# Lighting_Board.net
KiCad netlist of a schematic drawn in EAGLE
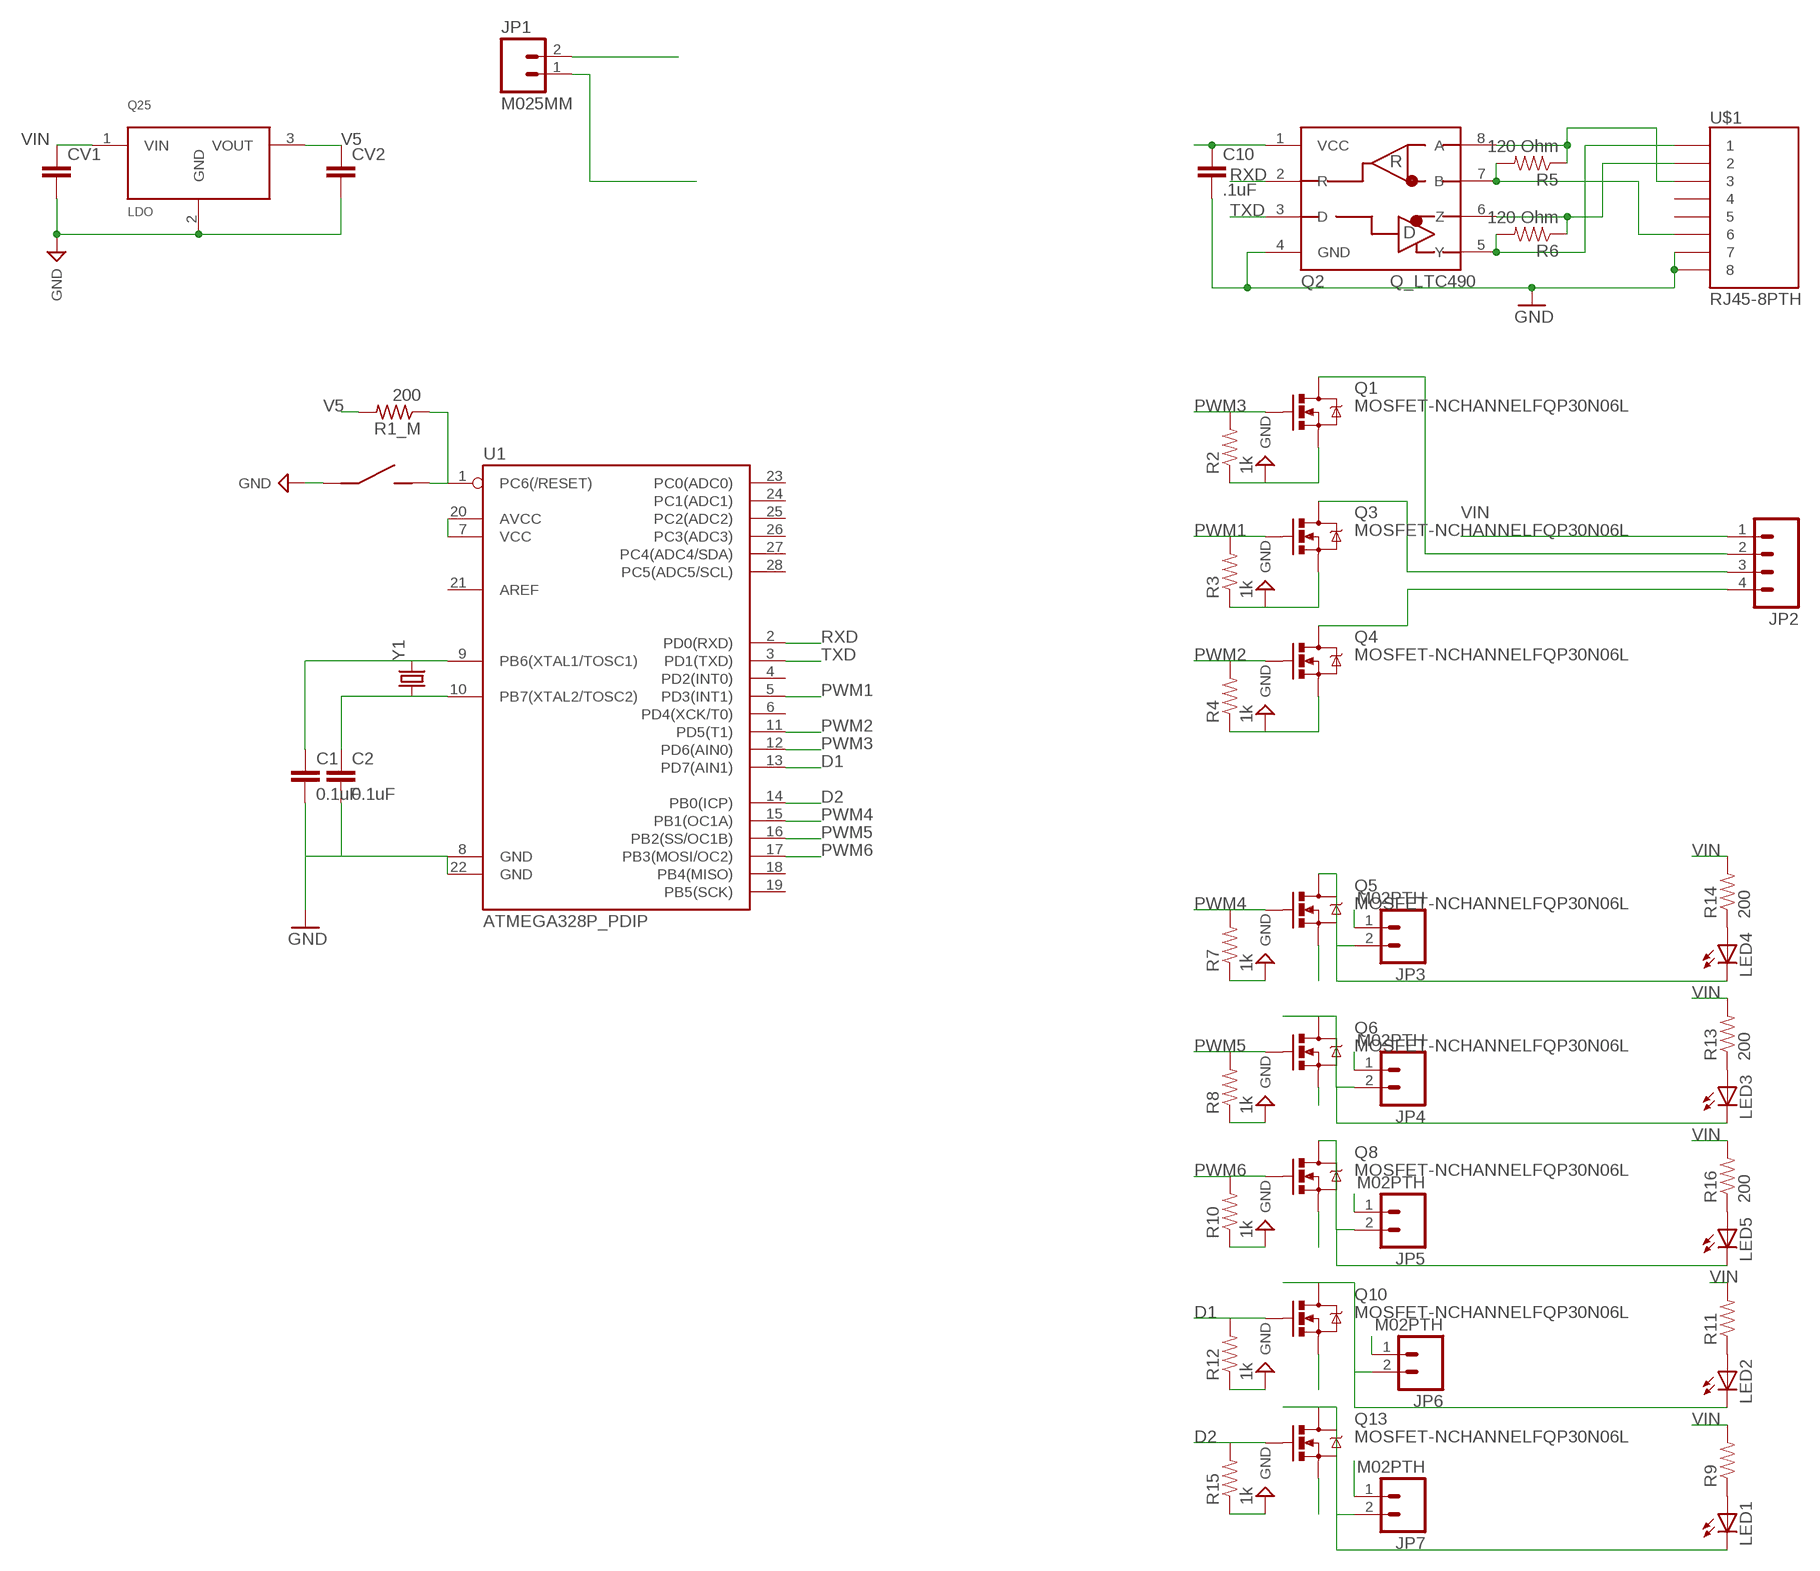
[diagram p0: schematic, sheet 1]

(export (version "E")
  (design (tool "Eeschema 10.0.6"))
  (components
    (comp (ref "C1")
      (value "0.1uF")
      (footprint "eagle-import:1206")
      (libsource (lib "eagle-import") (part "CAP1206"))
    )
    (comp (ref "C2")
      (value "0.1uF")
      (footprint "eagle-import:1206")
      (libsource (lib "eagle-import") (part "CAP1206"))
    )
    (comp (ref "C10")
      (value ".1uF")
      (footprint "eagle-import:1206")
      (libsource (lib "eagle-import") (part "2.2UF-CERCAP-10009"))
    )
    (comp (ref "CV1")
      (value "C_CAP_0805")
      (footprint "eagle-import:C_0805")
      (libsource (lib "eagle-import") (part "C_CAP_0805"))
    )
    (comp (ref "CV2")
      (value "C_CAP_0805")
      (footprint "eagle-import:C_0805")
      (libsource (lib "eagle-import") (part "C_CAP_0805"))
    )
    (comp (ref "JP1")
      (value "M025MM")
      (footprint "eagle-import:SCREWTERMINAL-5MM-2")
      (libsource (lib "eagle-import") (part "M025MM"))
    )
    (comp (ref "JP2")
      (value "M04PTH")
      (footprint "eagle-import:1X04")
      (libsource (lib "eagle-import") (part "M04PTH"))
    )
    (comp (ref "JP3")
      (value "M02PTH")
      (footprint "eagle-import:1X02")
      (libsource (lib "eagle-import") (part "M02PTH"))
    )
    (comp (ref "JP4")
      (value "M02PTH")
      (footprint "eagle-import:1X02")
      (libsource (lib "eagle-import") (part "M02PTH"))
    )
    (comp (ref "JP5")
      (value "M02PTH")
      (footprint "eagle-import:1X02")
      (libsource (lib "eagle-import") (part "M02PTH"))
    )
    (comp (ref "JP6")
      (value "M02PTH")
      (footprint "eagle-import:1X02")
      (libsource (lib "eagle-import") (part "M02PTH"))
    )
    (comp (ref "JP7")
      (value "M02PTH")
      (footprint "eagle-import:1X02")
      (libsource (lib "eagle-import") (part "M02PTH"))
    )
    (comp (ref "LED1")
      (value "LED1206")
      (footprint "eagle-import:LED-1206")
      (libsource (lib "eagle-import") (part "LED1206"))
    )
    (comp (ref "LED2")
      (value "LED1206")
      (footprint "eagle-import:LED-1206")
      (libsource (lib "eagle-import") (part "LED1206"))
    )
    (comp (ref "LED3")
      (value "LED1206")
      (footprint "eagle-import:LED-1206")
      (libsource (lib "eagle-import") (part "LED1206"))
    )
    (comp (ref "LED4")
      (value "LED1206")
      (footprint "eagle-import:LED-1206")
      (libsource (lib "eagle-import") (part "LED1206"))
    )
    (comp (ref "LED5")
      (value "LED1206")
      (footprint "eagle-import:LED-1206")
      (libsource (lib "eagle-import") (part "LED1206"))
    )
    (comp (ref "MS")
      (value "J_MC32857")
      (footprint "eagle-import:J_TOGGLE")
      (libsource (lib "eagle-import") (part "J_MC32857"))
    )
    (comp (ref "Q1")
      (value "MOSFET-NCHANNELFQP30N06L")
      (footprint "eagle-import:TO220V")
      (libsource (lib "eagle-import") (part "MOSFET-NCHANNELFQP30N06L"))
    )
    (comp (ref "Q2")
      (value "Q_LTC490")
      (footprint "eagle-import:DIP8")
      (libsource (lib "eagle-import") (part "Q_LTC490"))
    )
    (comp (ref "Q3")
      (value "MOSFET-NCHANNELFQP30N06L")
      (footprint "eagle-import:TO220V")
      (libsource (lib "eagle-import") (part "MOSFET-NCHANNELFQP30N06L"))
    )
    (comp (ref "Q4")
      (value "MOSFET-NCHANNELFQP30N06L")
      (footprint "eagle-import:TO220V")
      (libsource (lib "eagle-import") (part "MOSFET-NCHANNELFQP30N06L"))
    )
    (comp (ref "Q5")
      (value "MOSFET-NCHANNELFQP30N06L")
      (footprint "eagle-import:TO220V")
      (libsource (lib "eagle-import") (part "MOSFET-NCHANNELFQP30N06L"))
    )
    (comp (ref "Q6")
      (value "MOSFET-NCHANNELFQP30N06L")
      (footprint "eagle-import:TO220V")
      (libsource (lib "eagle-import") (part "MOSFET-NCHANNELFQP30N06L"))
    )
    (comp (ref "Q8")
      (value "MOSFET-NCHANNELFQP30N06L")
      (footprint "eagle-import:TO220V")
      (libsource (lib "eagle-import") (part "MOSFET-NCHANNELFQP30N06L"))
    )
    (comp (ref "Q10")
      (value "MOSFET-NCHANNELFQP30N06L")
      (footprint "eagle-import:TO220V")
      (libsource (lib "eagle-import") (part "MOSFET-NCHANNELFQP30N06L"))
    )
    (comp (ref "Q13")
      (value "MOSFET-NCHANNELFQP30N06L")
      (footprint "eagle-import:TO220V")
      (libsource (lib "eagle-import") (part "MOSFET-NCHANNELFQP30N06L"))
    )
    (comp (ref "Q25")
      (value "LDO")
      (footprint "eagle-import:TO-220")
      (libsource (lib "eagle-import") (part "Q_LDO"))
    )
    (comp (ref "R1_M")
      (value "200")
      (footprint "eagle-import:R_0805")
      (libsource (lib "eagle-import") (part "R_RES_0805"))
    )
    (comp (ref "R2")
      (value "1k")
      (footprint "eagle-import:1206")
      (libsource (lib "eagle-import") (part "RESISTOR1206"))
    )
    (comp (ref "R3")
      (value "1k")
      (footprint "eagle-import:1206")
      (libsource (lib "eagle-import") (part "RESISTOR1206"))
    )
    (comp (ref "R4")
      (value "1k")
      (footprint "eagle-import:1206")
      (libsource (lib "eagle-import") (part "RESISTOR1206"))
    )
    (comp (ref "R5")
      (value "120 Ohm")
      (footprint "eagle-import:1206")
      (libsource (lib "eagle-import") (part "RESISTOR1206"))
    )
    (comp (ref "R6")
      (value "120 Ohm")
      (footprint "eagle-import:1206")
      (libsource (lib "eagle-import") (part "RESISTOR1206"))
    )
    (comp (ref "R7")
      (value "1k")
      (footprint "eagle-import:1206")
      (libsource (lib "eagle-import") (part "RESISTOR1206"))
    )
    (comp (ref "R8")
      (value "1k")
      (footprint "eagle-import:1206")
      (libsource (lib "eagle-import") (part "RESISTOR1206"))
    )
    (comp (ref "R9")
      (value "RESISTOR1206")
      (footprint "eagle-import:1206")
      (libsource (lib "eagle-import") (part "RESISTOR1206"))
    )
    (comp (ref "R10")
      (value "1k")
      (footprint "eagle-import:1206")
      (libsource (lib "eagle-import") (part "RESISTOR1206"))
    )
    (comp (ref "R11")
      (value "RESISTOR1206")
      (footprint "eagle-import:1206")
      (libsource (lib "eagle-import") (part "RESISTOR1206"))
    )
    (comp (ref "R12")
      (value "1k")
      (footprint "eagle-import:1206")
      (libsource (lib "eagle-import") (part "RESISTOR1206"))
    )
    (comp (ref "R13")
      (value "200")
      (footprint "eagle-import:1206")
      (libsource (lib "eagle-import") (part "RESISTOR1206"))
    )
    (comp (ref "R14")
      (value "200")
      (footprint "eagle-import:1206")
      (libsource (lib "eagle-import") (part "RESISTOR1206"))
    )
    (comp (ref "R15")
      (value "1k")
      (footprint "eagle-import:1206")
      (libsource (lib "eagle-import") (part "RESISTOR1206"))
    )
    (comp (ref "R16")
      (value "200")
      (footprint "eagle-import:1206")
      (libsource (lib "eagle-import") (part "RESISTOR1206"))
    )
    (comp (ref "U$1")
      (value "RJ45-8PTH")
      (footprint "eagle-import:RJ45-8")
      (libsource (lib "eagle-import") (part "RJ45-8PTH"))
    )
    (comp (ref "U1")
      (value "ATMEGA328P_PDIP")
      (footprint "eagle-import:DIL28-3")
      (libsource (lib "eagle-import") (part "ATMEGA328P_PDIP"))
    )
    (comp (ref "Y1")
      (value "CRYSTALHC49US")
      (footprint "eagle-import:HC49US")
      (libsource (lib "eagle-import") (part "CRYSTALHC49US"))
    )
  )
  (nets
    (net (code "1") (name "/D1") (class "Default")
      (node (ref "Q10") (pin "1") (pinfunction "G_1") (pintype "passive"))
      (node (ref "R12") (pin "2") (pinfunction "2_2") (pintype "passive"))
      (node (ref "U1") (pin "13") (pinfunction "PD7(AIN1)_13") (pintype "bidirectional"))
    )
    (net (code "2") (name "/D2") (class "Default")
      (node (ref "Q13") (pin "1") (pinfunction "G_1") (pintype "passive"))
      (node (ref "R15") (pin "2") (pinfunction "2_2") (pintype "passive"))
      (node (ref "U1") (pin "14") (pinfunction "PB0(ICP)_14") (pintype "bidirectional"))
    )
    (net (code "3") (name "/PWM1") (class "Default")
      (node (ref "Q3") (pin "1") (pinfunction "G_1") (pintype "passive"))
      (node (ref "R3") (pin "2") (pinfunction "2_2") (pintype "passive"))
      (node (ref "U1") (pin "5") (pinfunction "PD3(INT1)_5") (pintype "bidirectional"))
    )
    (net (code "4") (name "/PWM2") (class "Default")
      (node (ref "Q4") (pin "1") (pinfunction "G_1") (pintype "passive"))
      (node (ref "R4") (pin "2") (pinfunction "2_2") (pintype "passive"))
      (node (ref "U1") (pin "11") (pinfunction "PD5(T1)_11") (pintype "bidirectional"))
    )
    (net (code "5") (name "/PWM3") (class "Default")
      (node (ref "Q1") (pin "1") (pinfunction "G_1") (pintype "passive"))
      (node (ref "R2") (pin "2") (pinfunction "2_2") (pintype "passive"))
      (node (ref "U1") (pin "12") (pinfunction "PD6(AIN0)_12") (pintype "bidirectional"))
    )
    (net (code "6") (name "/PWM4") (class "Default")
      (node (ref "Q5") (pin "1") (pinfunction "G_1") (pintype "passive"))
      (node (ref "R7") (pin "2") (pinfunction "2_2") (pintype "passive"))
      (node (ref "U1") (pin "15") (pinfunction "PB1(OC1A)_15") (pintype "bidirectional"))
    )
    (net (code "7") (name "/PWM5") (class "Default")
      (node (ref "Q6") (pin "1") (pinfunction "G_1") (pintype "passive"))
      (node (ref "R8") (pin "2") (pinfunction "2_2") (pintype "passive"))
      (node (ref "U1") (pin "16") (pinfunction "PB2(SS/OC1B)_16") (pintype "bidirectional"))
    )
    (net (code "8") (name "/PWM6") (class "Default")
      (node (ref "Q8") (pin "1") (pinfunction "G_1") (pintype "passive"))
      (node (ref "R10") (pin "2") (pinfunction "2_2") (pintype "passive"))
      (node (ref "U1") (pin "17") (pinfunction "PB3(MOSI/OC2)_17") (pintype "bidirectional"))
    )
    (net (code "9") (name "/RXD") (class "Default")
      (node (ref "Q2") (pin "2") (pinfunction "R_2") (pintype "bidirectional"))
      (node (ref "U1") (pin "2") (pinfunction "PD0(RXD)_2") (pintype "bidirectional"))
    )
    (net (code "10") (name "/TXD") (class "Default")
      (node (ref "Q2") (pin "3") (pinfunction "D_3") (pintype "bidirectional"))
      (node (ref "U1") (pin "3") (pinfunction "PD1(TXD)_3") (pintype "bidirectional"))
    )
    (net (code "11") (name "/V5") (class "Default")
      (node (ref "C10") (pin "1") (pinfunction "1_1") (pintype "passive"))
      (node (ref "CV2") (pin "1") (pinfunction "1_1") (pintype "passive"))
      (node (ref "Q2") (pin "1") (pinfunction "VCC_1") (pintype "bidirectional"))
      (node (ref "Q25") (pin "3") (pinfunction "VOUT_3") (pintype "bidirectional"))
      (node (ref "R1_M") (pin "2") (pinfunction "2_2") (pintype "passive"))
      (node (ref "U1") (pin "20") (pinfunction "AVCC_20") (pintype "bidirectional"))
      (node (ref "U1") (pin "7") (pinfunction "VCC_7") (pintype "bidirectional"))
    )
    (net (code "12") (name "/VIN") (class "Default")
      (node (ref "CV1") (pin "1") (pinfunction "1_1") (pintype "passive"))
      (node (ref "JP1") (pin "1") (pinfunction "1_1") (pintype "passive"))
      (node (ref "JP2") (pin "1") (pinfunction "1_1") (pintype "passive"))
      (node (ref "JP3") (pin "1") (pinfunction "1_1") (pintype "passive"))
      (node (ref "JP4") (pin "1") (pinfunction "1_1") (pintype "passive"))
      (node (ref "JP5") (pin "1") (pinfunction "1_1") (pintype "passive"))
      (node (ref "JP6") (pin "1") (pinfunction "1_1") (pintype "passive"))
      (node (ref "JP7") (pin "1") (pinfunction "1_1") (pintype "passive"))
      (node (ref "Q25") (pin "1") (pinfunction "VIN_1") (pintype "bidirectional"))
      (node (ref "R11") (pin "2") (pinfunction "2_2") (pintype "passive"))
      (node (ref "R13") (pin "2") (pinfunction "2_2") (pintype "passive"))
      (node (ref "R14") (pin "2") (pinfunction "2_2") (pintype "passive"))
      (node (ref "R16") (pin "2") (pinfunction "2_2") (pintype "passive"))
      (node (ref "R9") (pin "2") (pinfunction "2_2") (pintype "passive"))
    )
    (net (code "13") (name "GND") (class "Default")
      (node (ref "C1") (pin "2") (pinfunction "2_2") (pintype "passive"))
      (node (ref "C10") (pin "2") (pinfunction "2_2") (pintype "passive"))
      (node (ref "C2") (pin "2") (pinfunction "2_2") (pintype "passive"))
      (node (ref "CV1") (pin "2") (pinfunction "2_2") (pintype "passive"))
      (node (ref "CV2") (pin "2") (pinfunction "2_2") (pintype "passive"))
      (node (ref "JP1") (pin "2") (pinfunction "2_2") (pintype "passive"))
      (node (ref "MS") (pin "P$1") (pinfunction "1_P$1") (pintype "bidirectional"))
      (node (ref "Q1") (pin "3") (pinfunction "S_3") (pintype "passive"))
      (node (ref "Q10") (pin "3") (pinfunction "S_3") (pintype "passive"))
      (node (ref "Q13") (pin "3") (pinfunction "S_3") (pintype "passive"))
      (node (ref "Q2") (pin "4") (pinfunction "GND_4") (pintype "bidirectional"))
      (node (ref "Q25") (pin "2") (pinfunction "GND_2") (pintype "bidirectional"))
      (node (ref "Q3") (pin "3") (pinfunction "S_3") (pintype "passive"))
      (node (ref "Q4") (pin "3") (pinfunction "S_3") (pintype "passive"))
      (node (ref "Q5") (pin "3") (pinfunction "S_3") (pintype "passive"))
      (node (ref "Q6") (pin "3") (pinfunction "S_3") (pintype "passive"))
      (node (ref "Q8") (pin "3") (pinfunction "S_3") (pintype "passive"))
      (node (ref "R10") (pin "1") (pinfunction "1_1") (pintype "passive"))
      (node (ref "R12") (pin "1") (pinfunction "1_1") (pintype "passive"))
      (node (ref "R15") (pin "1") (pinfunction "1_1") (pintype "passive"))
      (node (ref "R2") (pin "1") (pinfunction "1_1") (pintype "passive"))
      (node (ref "R3") (pin "1") (pinfunction "1_1") (pintype "passive"))
      (node (ref "R4") (pin "1") (pinfunction "1_1") (pintype "passive"))
      (node (ref "R7") (pin "1") (pinfunction "1_1") (pintype "passive"))
      (node (ref "R8") (pin "1") (pinfunction "1_1") (pintype "passive"))
      (node (ref "U$1") (pin "7") (pinfunction "7_7") (pintype "bidirectional"))
      (node (ref "U$1") (pin "8") (pinfunction "8_8") (pintype "bidirectional"))
      (node (ref "U1") (pin "22") (pinfunction "GND_22") (pintype "bidirectional"))
      (node (ref "U1") (pin "8") (pinfunction "GND_8") (pintype "bidirectional"))
    )
    (net (code "14") (name "Net-(LED1-PadA)") (class "Default")
      (node (ref "LED1") (pin "A") (pinfunction "A_A") (pintype "passive"))
      (node (ref "R9") (pin "1") (pinfunction "1_1") (pintype "passive"))
    )
    (net (code "15") (name "Net-(LED2-PadA)") (class "Default")
      (node (ref "LED2") (pin "A") (pinfunction "A_A") (pintype "passive"))
      (node (ref "R11") (pin "1") (pinfunction "1_1") (pintype "passive"))
    )
    (net (code "16") (name "Net-(LED3-PadA)") (class "Default")
      (node (ref "LED3") (pin "A") (pinfunction "A_A") (pintype "passive"))
      (node (ref "R13") (pin "1") (pinfunction "1_1") (pintype "passive"))
    )
    (net (code "17") (name "Net-(LED4-PadA)") (class "Default")
      (node (ref "LED4") (pin "A") (pinfunction "A_A") (pintype "passive"))
      (node (ref "R14") (pin "1") (pinfunction "1_1") (pintype "passive"))
    )
    (net (code "18") (name "Net-(LED5-PadA)") (class "Default")
      (node (ref "LED5") (pin "A") (pinfunction "A_A") (pintype "passive"))
      (node (ref "R16") (pin "1") (pinfunction "1_1") (pintype "passive"))
    )
    (net (code "19") (name "Net-(MS-2)") (class "Default")
      (node (ref "MS") (pin "P$2") (pinfunction "2_P$2") (pintype "bidirectional"))
      (node (ref "R1_M") (pin "1") (pinfunction "1_1") (pintype "passive"))
      (node (ref "U1") (pin "1") (pinfunction "PC6(/RESET)_1") (pintype "bidirectional"))
    )
    (net (code "20") (name "Net-(Q1-D)") (class "Default")
      (node (ref "JP2") (pin "2") (pinfunction "2_2") (pintype "passive"))
      (node (ref "Q1") (pin "2") (pinfunction "D_2") (pintype "passive"))
    )
    (net (code "21") (name "Net-(Q2-A)") (class "Default")
      (node (ref "Q2") (pin "8") (pinfunction "A_8") (pintype "bidirectional"))
      (node (ref "R5") (pin "1") (pinfunction "1_1") (pintype "passive"))
      (node (ref "U$1") (pin "3") (pinfunction "3_3") (pintype "bidirectional"))
    )
    (net (code "22") (name "Net-(Q2-B)") (class "Default")
      (node (ref "Q2") (pin "7") (pinfunction "B_7") (pintype "bidirectional"))
      (node (ref "R5") (pin "2") (pinfunction "2_2") (pintype "passive"))
      (node (ref "U$1") (pin "6") (pinfunction "6_6") (pintype "bidirectional"))
    )
    (net (code "23") (name "Net-(Q2-Y)") (class "Default")
      (node (ref "Q2") (pin "5") (pinfunction "Y_5") (pintype "bidirectional"))
      (node (ref "R6") (pin "2") (pinfunction "2_2") (pintype "passive"))
      (node (ref "U$1") (pin "1") (pinfunction "1_1") (pintype "bidirectional"))
    )
    (net (code "24") (name "Net-(Q2-Z)") (class "Default")
      (node (ref "Q2") (pin "6") (pinfunction "Z_6") (pintype "bidirectional"))
      (node (ref "R6") (pin "1") (pinfunction "1_1") (pintype "passive"))
      (node (ref "U$1") (pin "2") (pinfunction "2_2") (pintype "bidirectional"))
    )
    (net (code "25") (name "Net-(Q3-D)") (class "Default")
      (node (ref "JP2") (pin "3") (pinfunction "3_3") (pintype "passive"))
      (node (ref "Q3") (pin "2") (pinfunction "D_2") (pintype "passive"))
    )
    (net (code "26") (name "Net-(Q4-D)") (class "Default")
      (node (ref "JP2") (pin "4") (pinfunction "4_4") (pintype "passive"))
      (node (ref "Q4") (pin "2") (pinfunction "D_2") (pintype "passive"))
    )
    (net (code "27") (name "Net-(Q5-D)") (class "Default")
      (node (ref "JP3") (pin "2") (pinfunction "2_2") (pintype "passive"))
      (node (ref "LED4") (pin "C") (pinfunction "C_C") (pintype "passive"))
      (node (ref "Q5") (pin "2") (pinfunction "D_2") (pintype "passive"))
    )
    (net (code "28") (name "Net-(Q6-D)") (class "Default")
      (node (ref "JP4") (pin "2") (pinfunction "2_2") (pintype "passive"))
      (node (ref "LED3") (pin "C") (pinfunction "C_C") (pintype "passive"))
      (node (ref "Q6") (pin "2") (pinfunction "D_2") (pintype "passive"))
    )
    (net (code "29") (name "Net-(Q8-D)") (class "Default")
      (node (ref "JP5") (pin "2") (pinfunction "2_2") (pintype "passive"))
      (node (ref "LED5") (pin "C") (pinfunction "C_C") (pintype "passive"))
      (node (ref "Q8") (pin "2") (pinfunction "D_2") (pintype "passive"))
    )
    (net (code "30") (name "Net-(Q10-D)") (class "Default")
      (node (ref "JP6") (pin "2") (pinfunction "2_2") (pintype "passive"))
      (node (ref "LED2") (pin "C") (pinfunction "C_C") (pintype "passive"))
      (node (ref "Q10") (pin "2") (pinfunction "D_2") (pintype "passive"))
    )
    (net (code "31") (name "Net-(Q13-D)") (class "Default")
      (node (ref "JP7") (pin "2") (pinfunction "2_2") (pintype "passive"))
      (node (ref "LED1") (pin "C") (pinfunction "C_C") (pintype "passive"))
      (node (ref "Q13") (pin "2") (pinfunction "D_2") (pintype "passive"))
    )
    (net (code "32") (name "Net-(U1-PB6(XTAL1{slash}TOSC1))") (class "Default")
      (node (ref "C1") (pin "1") (pinfunction "1_1") (pintype "passive"))
      (node (ref "U1") (pin "9") (pinfunction "PB6(XTAL1/TOSC1)_9") (pintype "bidirectional"))
      (node (ref "Y1") (pin "2") (pinfunction "2_2") (pintype "passive"))
    )
    (net (code "33") (name "Net-(U1-PB7(XTAL2{slash}TOSC2))") (class "Default")
      (node (ref "C2") (pin "1") (pinfunction "1_1") (pintype "passive"))
      (node (ref "U1") (pin "10") (pinfunction "PB7(XTAL2/TOSC2)_10") (pintype "bidirectional"))
      (node (ref "Y1") (pin "1") (pinfunction "1_1") (pintype "passive"))
    )
    (net (code "34") (name "unconnected-(U$1-Pad4)") (class "Default")
      (node (ref "U$1") (pin "4") (pinfunction "4_4") (pintype "bidirectional"))
    )
    (net (code "35") (name "unconnected-(U$1-Pad5)") (class "Default")
      (node (ref "U$1") (pin "5") (pinfunction "5_5") (pintype "bidirectional"))
    )
    (net (code "36") (name "unconnected-(U1-AREF-Pad21)") (class "Default")
      (node (ref "U1") (pin "21") (pinfunction "AREF_21") (pintype "bidirectional"))
    )
    (net (code "37") (name "unconnected-(U1-PB4(MISO)-Pad18)") (class "Default")
      (node (ref "U1") (pin "18") (pinfunction "PB4(MISO)_18") (pintype "bidirectional"))
    )
    (net (code "38") (name "unconnected-(U1-PB5(SCK)-Pad19)") (class "Default")
      (node (ref "U1") (pin "19") (pinfunction "PB5(SCK)_19") (pintype "bidirectional"))
    )
    (net (code "39") (name "unconnected-(U1-PC0(ADC0)-Pad23)") (class "Default")
      (node (ref "U1") (pin "23") (pinfunction "PC0(ADC0)_23") (pintype "bidirectional"))
    )
    (net (code "40") (name "unconnected-(U1-PC1(ADC1)-Pad24)") (class "Default")
      (node (ref "U1") (pin "24") (pinfunction "PC1(ADC1)_24") (pintype "bidirectional"))
    )
    (net (code "41") (name "unconnected-(U1-PC2(ADC2)-Pad25)") (class "Default")
      (node (ref "U1") (pin "25") (pinfunction "PC2(ADC2)_25") (pintype "bidirectional"))
    )
    (net (code "42") (name "unconnected-(U1-PC3(ADC3)-Pad26)") (class "Default")
      (node (ref "U1") (pin "26") (pinfunction "PC3(ADC3)_26") (pintype "bidirectional"))
    )
    (net (code "43") (name "unconnected-(U1-PC4(ADC4{slash}SDA)-Pad27)") (class "Default")
      (node (ref "U1") (pin "27") (pinfunction "PC4(ADC4/SDA)_27") (pintype "bidirectional"))
    )
    (net (code "44") (name "unconnected-(U1-PC5(ADC5{slash}SCL)-Pad28)") (class "Default")
      (node (ref "U1") (pin "28") (pinfunction "PC5(ADC5/SCL)_28") (pintype "bidirectional"))
    )
    (net (code "45") (name "unconnected-(U1-PD2(INT0)-Pad4)") (class "Default")
      (node (ref "U1") (pin "4") (pinfunction "PD2(INT0)_4") (pintype "bidirectional"))
    )
    (net (code "46") (name "unconnected-(U1-PD4(XCK{slash}T0)-Pad6)") (class "Default")
      (node (ref "U1") (pin "6") (pinfunction "PD4(XCK/T0)_6") (pintype "bidirectional"))
    )
  )
)
